# ESP32C6_Xbee.net
KiCad netlist of a schematic drawn in Altium Designer
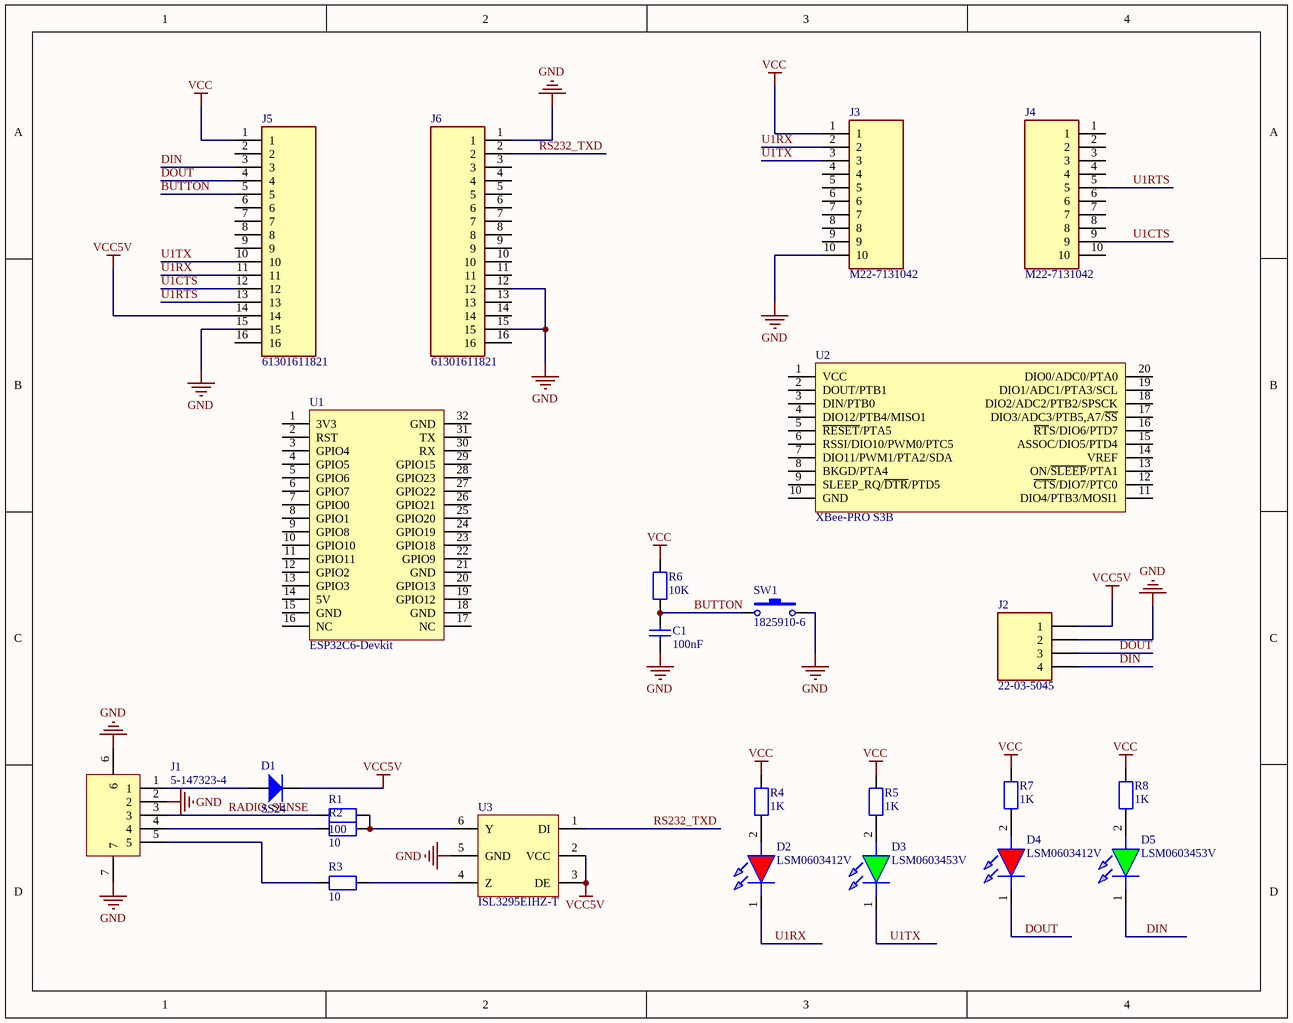
[diagram p0: ESP32C6_Xbee.SchDoc]

(export (version "E")
  (design (tool "Eeschema 10.0.6"))
  (components
    (comp (ref "C1")
      (value "100nF")
      (footprint "C0603")
      (description "0.1 µF ±10% 50V Ceramic Capacitor X7R 0603 (1608 Metric)")
      (fields
        (field (name "MANUFACTURER") "Yageo")
        (field (name "MANUFACTURER PART NUMBER") "CS0603KRX7R9BB104")
      )
      (libsource (lib "ESP32C6-Xbee") (part "100nF ± 10% 50V"))
    )
    (comp (ref "D1")
      (value "SS24")
      (footprint "DO-214AA")
      (description "Schottky Diodes & Rectifiers 2A, 40V, Schottky Rectifier")
      (fields (field (name "MANUFACTURER") "Taiwan Semiconductor"))
      (libsource (lib "ESP32C6-Xbee") (part "SS24"))
    )
    (comp (ref "D2")
      (value "LSM0603412V")
      (footprint "LSM0603412V")
      (description "Red 635nm LED Indication - Discrete 2V 0603 (1608 Metric)")
      (fields (field (name "MANUFACTURER") "Visual Communications Company"))
      (libsource (lib "ESP32C6-Xbee") (part "LSM0603412V"))
    )
    (comp (ref "D3")
      (value "LSM0603453V")
      (footprint "LEDC1608X55N")
      (description "Standard LEDs - SMD SMD 0603 3V 1000mcd GREEN")
      (fields (field (name "MANUFACTURER") "Visual Communications Company"))
      (libsource (lib "ESP32C6-Xbee") (part "LSM0603453V"))
    )
    (comp (ref "D4")
      (value "LSM0603412V")
      (footprint "LSM0603412V")
      (description "Red 635nm LED Indication - Discrete 2V 0603 (1608 Metric)")
      (fields (field (name "MANUFACTURER") "Visual Communications Company"))
      (libsource (lib "ESP32C6-Xbee") (part "LSM0603412V"))
    )
    (comp (ref "D5")
      (value "LSM0603453V")
      (footprint "LEDC1608X55N")
      (description "Standard LEDs - SMD SMD 0603 3V 1000mcd GREEN")
      (fields (field (name "MANUFACTURER") "Visual Communications Company"))
      (libsource (lib "ESP32C6-Xbee") (part "LSM0603453V"))
    )
    (comp (ref "J1")
      (value "5-147323-4")
      (footprint "5-147323-4")
      (description "Connector Header Surface Mount, Right Angle 5 position 0.100\" (2.54mm)")
      (fields (field (name "MANUFACTURER") "TE Connectivity"))
      (libsource (lib "ESP32C6-Xbee") (part "5-147323-4"))
    )
    (comp (ref "J2")
      (value "22-03-5045")
      (footprint "MOLEX_22-03-5045")
      (description "Headers & Wire Housings 2.5 VERT HDR SPOX 4P shrouded")
      (fields (field (name "MANUFACTURER") "Molex"))
      (libsource (lib "ESP32C6-Xbee") (part "22-03-5045"))
    )
    (comp (ref "J3")
      (value "M22-7131042")
      (footprint "M22-7131042")
      (fields (field (name "MANUFACTURER") "Harwin"))
      (libsource (lib "") (part "M22-7131042_1"))
    )
    (comp (ref "J4")
      (value "M22-7131042")
      (footprint "M22-7131042")
      (fields (field (name "MANUFACTURER") "Harwin"))
      (libsource (lib "ESP32C6-Xbee") (part "M22-7131042"))
    )
    (comp (ref "J5")
      (value "61301611821")
      (footprint "61301611821")
      (description "16 Position Header Connector 0.100\" (2.54mm) Through Hole Gold")
      (fields (field (name "MANUFACTURER") "Wurth Elektronik"))
      (libsource (lib "ESP32C6-Xbee") (part "61301611821"))
    )
    (comp (ref "J6")
      (value "61301611821")
      (footprint "61301611821")
      (description "16 Position Header Connector 0.100\" (2.54mm) Through Hole Gold")
      (fields (field (name "MANUFACTURER") "Wurth Elektronik"))
      (libsource (lib "") (part "61301611821_1"))
    )
    (comp (ref "R1")
      (value "100")
      (footprint "R0603")
      (description "100 Ohms ±1% 0.1W, 1/10W Chip Resistor 0603 (1608 Metric) Moisture Resistant Thick Film")
      (fields
        (field (name "MANUFACTURER") "Yageo")
        (field (name "MANUFACTURER PART NUMBER") "RC0603FR-07100RL")
      )
      (libsource (lib "ESP32C6-Xbee") (part "100 Ohms ±1% 0.1W"))
    )
    (comp (ref "R2")
      (value "10")
      (footprint "R0603")
      (description "10 Ohms ±1% 0.1W, 1/10W Chip Resistor 0603 (1608 Metric) Moisture Resistant Thick Film")
      (fields
        (field (name "MANUFACTURER") "Yageo")
        (field (name "MANUFACTURER PART NUMBER") "RC0603FR-0710RL")
      )
      (libsource (lib "ESP32C6-Xbee") (part "10 Ohms ±1% 0.1W"))
    )
    (comp (ref "R3")
      (value "10")
      (footprint "R0603")
      (description "10 Ohms ±1% 0.1W, 1/10W Chip Resistor 0603 (1608 Metric) Moisture Resistant Thick Film")
      (fields
        (field (name "MANUFACTURER") "Yageo")
        (field (name "MANUFACTURER PART NUMBER") "RC0603FR-0710RL")
      )
      (libsource (lib "ESP32C6-Xbee") (part "10 Ohms ±1% 0.1W"))
    )
    (comp (ref "R4")
      (value "1K")
      (footprint "R0603")
      (description "1 kOhms ±1% 0.1W, 1/10W Chip Resistor 0603 (1608 Metric) Moisture Resistant Thick Film")
      (fields
        (field (name "MANUFACTURER") "Yageo")
        (field (name "MANUFACTURER PART NUMBER") "RC0603FR-071KL")
      )
      (libsource (lib "ESP32C6-Xbee") (part "1K Ohms ±1% 0.1W"))
    )
    (comp (ref "R5")
      (value "1K")
      (footprint "R0603")
      (description "1 kOhms ±1% 0.1W, 1/10W Chip Resistor 0603 (1608 Metric) Moisture Resistant Thick Film")
      (fields
        (field (name "MANUFACTURER") "Yageo")
        (field (name "MANUFACTURER PART NUMBER") "RC0603FR-071KL")
      )
      (libsource (lib "ESP32C6-Xbee") (part "1K Ohms ±1% 0.1W"))
    )
    (comp (ref "R6")
      (value "10K")
      (footprint "R0603")
      (description "10 kOhms ±1% 0.1W, 1/10W Chip Resistor 0603 (1608 Metric) Moisture Resistant Thick Film")
      (fields
        (field (name "MANUFACTURER") "Yageo")
        (field (name "MANUFACTURER PART NUMBER") "RC0603FR-0710KL")
      )
      (libsource (lib "ESP32C6-Xbee") (part "10K Ohms ±1% 0.1W"))
    )
    (comp (ref "R7")
      (value "1K")
      (footprint "R0603")
      (description "1 kOhms ±1% 0.1W, 1/10W Chip Resistor 0603 (1608 Metric) Moisture Resistant Thick Film")
      (fields
        (field (name "MANUFACTURER") "Yageo")
        (field (name "MANUFACTURER PART NUMBER") "RC0603FR-071KL")
      )
      (libsource (lib "ESP32C6-Xbee") (part "1K Ohms ±1% 0.1W"))
    )
    (comp (ref "R8")
      (value "1K")
      (footprint "R0603")
      (description "1 kOhms ±1% 0.1W, 1/10W Chip Resistor 0603 (1608 Metric) Moisture Resistant Thick Film")
      (fields
        (field (name "MANUFACTURER") "Yageo")
        (field (name "MANUFACTURER PART NUMBER") "RC0603FR-071KL")
      )
      (libsource (lib "ESP32C6-Xbee") (part "1K Ohms ±1% 0.1W"))
    )
    (comp (ref "SW1")
      (value "1825910-6")
      (footprint "SW_1825910-6-4")
      (description "Tactile Switch SPST-NO Top Actuated Through Hole")
      (fields (field (name "MANUFACTURER") "TE Connectivity"))
      (libsource (lib "ESP32C6-Xbee") (part "1825910-6"))
    )
    (comp (ref "U1")
      (value "ESP32C6-Devkit")
      (footprint "ESP32-C6-Devkit")
      (description "ESP32-C6-MINI-1 Transceiver; Bluetooth® 5 2.4GHz Evaluation Board")
      (fields
        (field (name "MANUFACTURER") "Espressif Systems")
        (field (name "MANUFACTURER PART NUMBER") "ESP32-C6-DevKitM-1-N4")
      )
      (libsource (lib "ESP32C6-Xbee") (part "ESP32C6-Devkit"))
    )
    (comp (ref "U2")
      (value "XBee-PRO S3B")
      (footprint "XBEE(MMS-110-02-L-SV-K-TR)")
      (description "General ISM < 1GHz Transceiver Module 920MHz Antenna Not Included, RP-SMA Through Hole")
      (fields (field (name "MANUFACTURER") "DIGI") (field (name "MANUFACTURER PART NUMBER") "XBP9B-XCST-022"))
      (libsource (lib "ESP32C6-Xbee") (part "XBee-PRO S3B"))
    )
    (comp (ref "U3")
      (value "ISL3295EIHZ-T")
      (footprint "SOT23-6")
      (description "1/0 Driver RS422, RS485 6-SOT")
      (fields (field (name "MANUFACTURER") "Renesas Electronics America Inc"))
      (libsource (lib "ESP32C6-Xbee") (part "ISL3295EIHZ-T"))
    )
  )
  (nets
    (net (code "1") (name "/BUTTON") (class "Default")
      (node (ref "C1") (pin "2") (pinfunction "2_2") (pintype "passive"))
      (node (ref "J5") (pin "5") (pinfunction "5_5") (pintype "passive"))
      (node (ref "R6") (pin "1") (pinfunction "1_1") (pintype "passive"))
      (node (ref "SW1") (pin "1") (pinfunction "1_1") (pintype "passive"))
    )
    (net (code "2") (name "/DIN") (class "Default")
      (node (ref "D5") (pin "1") (pinfunction "K_1") (pintype "passive"))
      (node (ref "J2") (pin "4") (pinfunction "4_4") (pintype "passive"))
      (node (ref "J5") (pin "3") (pinfunction "3_3") (pintype "passive"))
    )
    (net (code "3") (name "/DOUT") (class "Default")
      (node (ref "D4") (pin "1") (pinfunction "K_1") (pintype "passive"))
      (node (ref "J2") (pin "3") (pinfunction "3_3") (pintype "passive"))
      (node (ref "J5") (pin "4") (pinfunction "4_4") (pintype "passive"))
    )
    (net (code "4") (name "/RADIO_SENSE") (class "Default")
      (node (ref "J1") (pin "3") (pinfunction "3_3") (pintype "passive"))
      (node (ref "R1") (pin "1") (pinfunction "1_1") (pintype "passive"))
    )
    (net (code "5") (name "/RS232_TXD") (class "Default")
      (node (ref "J6") (pin "2") (pinfunction "2_2") (pintype "passive"))
      (node (ref "U3") (pin "1") (pinfunction "DI_1") (pintype "passive"))
    )
    (net (code "6") (name "/U1CTS") (class "Default")
      (node (ref "J4") (pin "9") (pinfunction "9_9") (pintype "passive"))
      (node (ref "J5") (pin "12") (pinfunction "12_12") (pintype "passive"))
    )
    (net (code "7") (name "/U1RTS") (class "Default")
      (node (ref "J4") (pin "5") (pinfunction "5_5") (pintype "passive"))
      (node (ref "J5") (pin "13") (pinfunction "13_13") (pintype "passive"))
    )
    (net (code "8") (name "/U1RX") (class "Default")
      (node (ref "D2") (pin "1") (pinfunction "K_1") (pintype "passive"))
      (node (ref "J3") (pin "2") (pinfunction "2_2") (pintype "passive"))
      (node (ref "J5") (pin "11") (pinfunction "11_11") (pintype "passive"))
    )
    (net (code "9") (name "/U1TX") (class "Default")
      (node (ref "D3") (pin "1") (pinfunction "K_1") (pintype "passive"))
      (node (ref "J3") (pin "3") (pinfunction "3_3") (pintype "passive"))
      (node (ref "J5") (pin "10") (pinfunction "10_10") (pintype "passive"))
    )
    (net (code "10") (name "GND") (class "Default")
      (node (ref "C1") (pin "1") (pinfunction "1_1") (pintype "passive"))
      (node (ref "J1") (pin "2") (pinfunction "2_2") (pintype "passive"))
      (node (ref "J1") (pin "6") (pinfunction "6_6") (pintype "passive"))
      (node (ref "J1") (pin "7") (pinfunction "7_7") (pintype "passive"))
      (node (ref "J2") (pin "2") (pinfunction "2_2") (pintype "passive"))
      (node (ref "J3") (pin "10") (pinfunction "10_10") (pintype "passive"))
      (node (ref "J5") (pin "15") (pinfunction "15_15") (pintype "passive"))
      (node (ref "J6") (pin "1") (pinfunction "1_1") (pintype "passive"))
      (node (ref "J6") (pin "12") (pinfunction "12_12") (pintype "passive"))
      (node (ref "J6") (pin "15") (pinfunction "15_15") (pintype "passive"))
      (node (ref "SW1") (pin "2") (pinfunction "2_2") (pintype "passive"))
      (node (ref "U3") (pin "5") (pinfunction "GND_5") (pintype "passive"))
    )
    (net (code "11") (name "Net-(D1-Pad1)") (class "Default")
      (node (ref "D1") (pin "1") (pintype "passive"))
      (node (ref "J1") (pin "1") (pinfunction "1_1") (pintype "passive"))
    )
    (net (code "12") (name "Net-(D2-A)") (class "Default")
      (node (ref "D2") (pin "2") (pinfunction "A_2") (pintype "passive"))
      (node (ref "R4") (pin "1") (pinfunction "1_1") (pintype "passive"))
    )
    (net (code "13") (name "Net-(D3-A)") (class "Default")
      (node (ref "D3") (pin "2") (pinfunction "A_2") (pintype "passive"))
      (node (ref "R5") (pin "1") (pinfunction "1_1") (pintype "passive"))
    )
    (net (code "14") (name "Net-(D4-A)") (class "Default")
      (node (ref "D4") (pin "2") (pinfunction "A_2") (pintype "passive"))
      (node (ref "R7") (pin "1") (pinfunction "1_1") (pintype "passive"))
    )
    (net (code "15") (name "Net-(D5-A)") (class "Default")
      (node (ref "D5") (pin "2") (pinfunction "A_2") (pintype "passive"))
      (node (ref "R8") (pin "1") (pinfunction "1_1") (pintype "passive"))
    )
    (net (code "16") (name "Net-(J1-Pad4)") (class "Default")
      (node (ref "J1") (pin "4") (pinfunction "4_4") (pintype "passive"))
      (node (ref "R2") (pin "1") (pinfunction "1_1") (pintype "passive"))
    )
    (net (code "17") (name "Net-(J1-Pad5)") (class "Default")
      (node (ref "J1") (pin "5") (pinfunction "5_5") (pintype "passive"))
      (node (ref "R3") (pin "1") (pinfunction "1_1") (pintype "passive"))
    )
    (net (code "18") (name "Net-(U3-Y)") (class "Default")
      (node (ref "R1") (pin "2") (pinfunction "2_2") (pintype "passive"))
      (node (ref "R2") (pin "2") (pinfunction "2_2") (pintype "passive"))
      (node (ref "U3") (pin "6") (pinfunction "Y_6") (pintype "passive"))
    )
    (net (code "19") (name "Net-(U3-Z)") (class "Default")
      (node (ref "R3") (pin "2") (pinfunction "2_2") (pintype "passive"))
      (node (ref "U3") (pin "4") (pinfunction "Z_4") (pintype "passive"))
    )
    (net (code "20") (name "VCC") (class "Default")
      (node (ref "J3") (pin "1") (pinfunction "1_1") (pintype "passive"))
      (node (ref "J5") (pin "1") (pinfunction "1_1") (pintype "passive"))
      (node (ref "R4") (pin "2") (pinfunction "2_2") (pintype "passive"))
      (node (ref "R5") (pin "2") (pinfunction "2_2") (pintype "passive"))
      (node (ref "R6") (pin "2") (pinfunction "2_2") (pintype "passive"))
      (node (ref "R7") (pin "2") (pinfunction "2_2") (pintype "passive"))
      (node (ref "R8") (pin "2") (pinfunction "2_2") (pintype "passive"))
    )
    (net (code "21") (name "VCC5V") (class "Default")
      (node (ref "D1") (pin "2") (pintype "passive"))
      (node (ref "J2") (pin "1") (pinfunction "1_1") (pintype "passive"))
      (node (ref "J5") (pin "14") (pinfunction "14_14") (pintype "passive"))
      (node (ref "U3") (pin "2") (pinfunction "VCC_2") (pintype "passive"))
      (node (ref "U3") (pin "3") (pinfunction "DE_3") (pintype "passive"))
    )
    (net (code "22") (name "unconnected-(J3-Pad4)") (class "Default")
      (node (ref "J3") (pin "4") (pinfunction "4_4") (pintype "passive"))
    )
    (net (code "23") (name "unconnected-(J3-Pad5)") (class "Default")
      (node (ref "J3") (pin "5") (pinfunction "5_5") (pintype "passive"))
    )
    (net (code "24") (name "unconnected-(J3-Pad6)") (class "Default")
      (node (ref "J3") (pin "6") (pinfunction "6_6") (pintype "passive"))
    )
    (net (code "25") (name "unconnected-(J3-Pad7)") (class "Default")
      (node (ref "J3") (pin "7") (pinfunction "7_7") (pintype "passive"))
    )
    (net (code "26") (name "unconnected-(J3-Pad8)") (class "Default")
      (node (ref "J3") (pin "8") (pinfunction "8_8") (pintype "passive"))
    )
    (net (code "27") (name "unconnected-(J3-Pad9)") (class "Default")
      (node (ref "J3") (pin "9") (pinfunction "9_9") (pintype "passive"))
    )
    (net (code "28") (name "unconnected-(J4-Pad1)") (class "Default")
      (node (ref "J4") (pin "1") (pinfunction "1_1") (pintype "passive"))
    )
    (net (code "29") (name "unconnected-(J4-Pad2)") (class "Default")
      (node (ref "J4") (pin "2") (pinfunction "2_2") (pintype "passive"))
    )
    (net (code "30") (name "unconnected-(J4-Pad3)") (class "Default")
      (node (ref "J4") (pin "3") (pinfunction "3_3") (pintype "passive"))
    )
    (net (code "31") (name "unconnected-(J4-Pad4)") (class "Default")
      (node (ref "J4") (pin "4") (pinfunction "4_4") (pintype "passive"))
    )
    (net (code "32") (name "unconnected-(J4-Pad6)") (class "Default")
      (node (ref "J4") (pin "6") (pinfunction "6_6") (pintype "passive"))
    )
    (net (code "33") (name "unconnected-(J4-Pad7)") (class "Default")
      (node (ref "J4") (pin "7") (pinfunction "7_7") (pintype "passive"))
    )
    (net (code "34") (name "unconnected-(J4-Pad8)") (class "Default")
      (node (ref "J4") (pin "8") (pinfunction "8_8") (pintype "passive"))
    )
    (net (code "35") (name "unconnected-(J4-Pad10)") (class "Default")
      (node (ref "J4") (pin "10") (pinfunction "10_10") (pintype "passive"))
    )
    (net (code "36") (name "unconnected-(J5-Pad2)") (class "Default")
      (node (ref "J5") (pin "2") (pinfunction "2_2") (pintype "passive"))
    )
    (net (code "37") (name "unconnected-(J5-Pad6)") (class "Default")
      (node (ref "J5") (pin "6") (pinfunction "6_6") (pintype "passive"))
    )
    (net (code "38") (name "unconnected-(J5-Pad7)") (class "Default")
      (node (ref "J5") (pin "7") (pinfunction "7_7") (pintype "passive"))
    )
    (net (code "39") (name "unconnected-(J5-Pad8)") (class "Default")
      (node (ref "J5") (pin "8") (pinfunction "8_8") (pintype "passive"))
    )
    (net (code "40") (name "unconnected-(J5-Pad9)") (class "Default")
      (node (ref "J5") (pin "9") (pinfunction "9_9") (pintype "passive"))
    )
    (net (code "41") (name "unconnected-(J5-Pad16)") (class "Default")
      (node (ref "J5") (pin "16") (pinfunction "16_16") (pintype "passive"))
    )
    (net (code "42") (name "unconnected-(J6-Pad3)") (class "Default")
      (node (ref "J6") (pin "3") (pinfunction "3_3") (pintype "passive"))
    )
    (net (code "43") (name "unconnected-(J6-Pad4)") (class "Default")
      (node (ref "J6") (pin "4") (pinfunction "4_4") (pintype "passive"))
    )
    (net (code "44") (name "unconnected-(J6-Pad5)") (class "Default")
      (node (ref "J6") (pin "5") (pinfunction "5_5") (pintype "passive"))
    )
    (net (code "45") (name "unconnected-(J6-Pad6)") (class "Default")
      (node (ref "J6") (pin "6") (pinfunction "6_6") (pintype "passive"))
    )
    (net (code "46") (name "unconnected-(J6-Pad7)") (class "Default")
      (node (ref "J6") (pin "7") (pinfunction "7_7") (pintype "passive"))
    )
    (net (code "47") (name "unconnected-(J6-Pad8)") (class "Default")
      (node (ref "J6") (pin "8") (pinfunction "8_8") (pintype "passive"))
    )
    (net (code "48") (name "unconnected-(J6-Pad9)") (class "Default")
      (node (ref "J6") (pin "9") (pinfunction "9_9") (pintype "passive"))
    )
    (net (code "49") (name "unconnected-(J6-Pad10)") (class "Default")
      (node (ref "J6") (pin "10") (pinfunction "10_10") (pintype "passive"))
    )
    (net (code "50") (name "unconnected-(J6-Pad11)") (class "Default")
      (node (ref "J6") (pin "11") (pinfunction "11_11") (pintype "passive"))
    )
    (net (code "51") (name "unconnected-(J6-Pad13)") (class "Default")
      (node (ref "J6") (pin "13") (pinfunction "13_13") (pintype "passive"))
    )
    (net (code "52") (name "unconnected-(J6-Pad14)") (class "Default")
      (node (ref "J6") (pin "14") (pinfunction "14_14") (pintype "passive"))
    )
    (net (code "53") (name "unconnected-(J6-Pad16)") (class "Default")
      (node (ref "J6") (pin "16") (pinfunction "16_16") (pintype "passive"))
    )
    (net (code "54") (name "unconnected-(U1-3V3-Pad1)") (class "Default")
      (node (ref "U1") (pin "1") (pinfunction "3V3_1") (pintype "passive"))
    )
    (net (code "55") (name "unconnected-(U1-5V-Pad14)") (class "Default")
      (node (ref "U1") (pin "14") (pinfunction "5V_14") (pintype "passive"))
    )
    (net (code "56") (name "unconnected-(U1-GND-Pad15)") (class "Default")
      (node (ref "U1") (pin "15") (pinfunction "GND_15") (pintype "passive"))
    )
    (net (code "57") (name "unconnected-(U1-GND-Pad18)") (class "Default")
      (node (ref "U1") (pin "18") (pinfunction "GND_18") (pintype "passive"))
    )
    (net (code "58") (name "unconnected-(U1-GND-Pad21)") (class "Default")
      (node (ref "U1") (pin "21") (pinfunction "GND_21") (pintype "passive"))
    )
    (net (code "59") (name "unconnected-(U1-GND-Pad32)") (class "Default")
      (node (ref "U1") (pin "32") (pinfunction "GND_32") (pintype "passive"))
    )
    (net (code "60") (name "unconnected-(U1-GPIO0-Pad7)") (class "Default")
      (node (ref "U1") (pin "7") (pinfunction "GPIO0_7") (pintype "passive"))
    )
    (net (code "61") (name "unconnected-(U1-GPIO1-Pad8)") (class "Default")
      (node (ref "U1") (pin "8") (pinfunction "GPIO1_8") (pintype "passive"))
    )
    (net (code "62") (name "unconnected-(U1-GPIO2-Pad12)") (class "Default")
      (node (ref "U1") (pin "12") (pinfunction "GPIO2_12") (pintype "passive"))
    )
    (net (code "63") (name "unconnected-(U1-GPIO3-Pad13)") (class "Default")
      (node (ref "U1") (pin "13") (pinfunction "GPIO3_13") (pintype "passive"))
    )
    (net (code "64") (name "unconnected-(U1-GPIO4-Pad3)") (class "Default")
      (node (ref "U1") (pin "3") (pinfunction "GPIO4_3") (pintype "passive"))
    )
    (net (code "65") (name "unconnected-(U1-GPIO5-Pad4)") (class "Default")
      (node (ref "U1") (pin "4") (pinfunction "GPIO5_4") (pintype "passive"))
    )
    (net (code "66") (name "unconnected-(U1-GPIO6-Pad5)") (class "Default")
      (node (ref "U1") (pin "5") (pinfunction "GPIO6_5") (pintype "passive"))
    )
    (net (code "67") (name "unconnected-(U1-GPIO7-Pad6)") (class "Default")
      (node (ref "U1") (pin "6") (pinfunction "GPIO7_6") (pintype "passive"))
    )
    (net (code "68") (name "unconnected-(U1-GPIO8-Pad9)") (class "Default")
      (node (ref "U1") (pin "9") (pinfunction "GPIO8_9") (pintype "passive"))
    )
    (net (code "69") (name "unconnected-(U1-GPIO9-Pad22)") (class "Default")
      (node (ref "U1") (pin "22") (pinfunction "GPIO9_22") (pintype "passive"))
    )
    (net (code "70") (name "unconnected-(U1-GPIO10-Pad10)") (class "Default")
      (node (ref "U1") (pin "10") (pinfunction "GPIO10_10") (pintype "passive"))
    )
    (net (code "71") (name "unconnected-(U1-GPIO11-Pad11)") (class "Default")
      (node (ref "U1") (pin "11") (pinfunction "GPIO11_11") (pintype "passive"))
    )
    (net (code "72") (name "unconnected-(U1-GPIO12-Pad19)") (class "Default")
      (node (ref "U1") (pin "19") (pinfunction "GPIO12_19") (pintype "passive"))
    )
    (net (code "73") (name "unconnected-(U1-GPIO13-Pad20)") (class "Default")
      (node (ref "U1") (pin "20") (pinfunction "GPIO13_20") (pintype "passive"))
    )
    (net (code "74") (name "unconnected-(U1-GPIO15-Pad29)") (class "Default")
      (node (ref "U1") (pin "29") (pinfunction "GPIO15_29") (pintype "passive"))
    )
    (net (code "75") (name "unconnected-(U1-GPIO18-Pad23)") (class "Default")
      (node (ref "U1") (pin "23") (pinfunction "GPIO18_23") (pintype "passive"))
    )
    (net (code "76") (name "unconnected-(U1-GPIO19-Pad24)") (class "Default")
      (node (ref "U1") (pin "24") (pinfunction "GPIO19_24") (pintype "passive"))
    )
    (net (code "77") (name "unconnected-(U1-GPIO20-Pad25)") (class "Default")
      (node (ref "U1") (pin "25") (pinfunction "GPIO20_25") (pintype "passive"))
    )
    (net (code "78") (name "unconnected-(U1-GPIO21-Pad26)") (class "Default")
      (node (ref "U1") (pin "26") (pinfunction "GPIO21_26") (pintype "passive"))
    )
    (net (code "79") (name "unconnected-(U1-GPIO22-Pad27)") (class "Default")
      (node (ref "U1") (pin "27") (pinfunction "GPIO22_27") (pintype "passive"))
    )
    (net (code "80") (name "unconnected-(U1-GPIO23-Pad28)") (class "Default")
      (node (ref "U1") (pin "28") (pinfunction "GPIO23_28") (pintype "passive"))
    )
    (net (code "81") (name "unconnected-(U1-NC-Pad16)") (class "Default")
      (node (ref "U1") (pin "16") (pinfunction "NC_16") (pintype "passive"))
    )
    (net (code "82") (name "unconnected-(U1-NC-Pad17)") (class "Default")
      (node (ref "U1") (pin "17") (pinfunction "NC_17") (pintype "passive"))
    )
    (net (code "83") (name "unconnected-(U1-RST-Pad2)") (class "Default")
      (node (ref "U1") (pin "2") (pinfunction "RST_2") (pintype "passive"))
    )
    (net (code "84") (name "unconnected-(U1-RX-Pad30)") (class "Default")
      (node (ref "U1") (pin "30") (pinfunction "RX_30") (pintype "passive"))
    )
    (net (code "85") (name "unconnected-(U1-TX-Pad31)") (class "Default")
      (node (ref "U1") (pin "31") (pinfunction "TX_31") (pintype "passive"))
    )
    (net (code "86") (name "unconnected-(U2-ASSOC{slash}DIO5{slash}PTD4-Pad15)") (class "Default")
      (node (ref "U2") (pin "15") (pinfunction "ASSOC/DIO5/PTD4_15") (pintype "passive"))
    )
    (net (code "87") (name "unconnected-(U2-BKGD{slash}PTA4-Pad8)") (class "Default")
      (node (ref "U2") (pin "8") (pinfunction "BKGD/PTA4_8") (pintype "passive"))
    )
    (net (code "88") (name "unconnected-(U2-DIN{slash}PTB0-Pad3)") (class "Default")
      (node (ref "U2") (pin "3") (pinfunction "DIN/PTB0_3") (pintype "passive"))
    )
    (net (code "89") (name "unconnected-(U2-DIO0{slash}ADC0{slash}PTA0-Pad20)") (class "Default")
      (node (ref "U2") (pin "20") (pinfunction "DIO0/ADC0/PTA0_20") (pintype "passive"))
    )
    (net (code "90") (name "unconnected-(U2-DIO1{slash}ADC1{slash}PTA3{slash}SCL-Pad19)") (class "Default")
      (node (ref "U2") (pin "19") (pinfunction "DIO1/ADC1/PTA3/SCL_19") (pintype "passive"))
    )
    (net (code "91") (name "unconnected-(U2-DIO2{slash}ADC2{slash}PTB2{slash}SPSCK-Pad18)") (class "Default")
      (node (ref "U2") (pin "18") (pinfunction "DIO2/ADC2/PTB2/SPSCK_18") (pintype "passive"))
    )
    (net (code "92") (name "unconnected-(U2-DIO3{slash}ADC3{slash}PTB5,A7{slash}~{SS}-Pad17)") (class "Default")
      (node (ref "U2") (pin "17") (pinfunction "DIO3/ADC3/PTB5,A7/~{SS}_17") (pintype "passive"))
    )
    (net (code "93") (name "unconnected-(U2-DIO4{slash}PTB3{slash}MOSI1-Pad11)") (class "Default")
      (node (ref "U2") (pin "11") (pinfunction "DIO4/PTB3/MOSI1_11") (pintype "passive"))
    )
    (net (code "94") (name "unconnected-(U2-DIO11{slash}PWM1{slash}PTA2{slash}SDA-Pad7)") (class "Default")
      (node (ref "U2") (pin "7") (pinfunction "DIO11/PWM1/PTA2/SDA_7") (pintype "passive"))
    )
    (net (code "95") (name "unconnected-(U2-DIO12{slash}PTB4{slash}MISO1-Pad4)") (class "Default")
      (node (ref "U2") (pin "4") (pinfunction "DIO12/PTB4/MISO1_4") (pintype "passive"))
    )
    (net (code "96") (name "unconnected-(U2-DOUT{slash}PTB1-Pad2)") (class "Default")
      (node (ref "U2") (pin "2") (pinfunction "DOUT/PTB1_2") (pintype "passive"))
    )
    (net (code "97") (name "unconnected-(U2-GND-Pad10)") (class "Default")
      (node (ref "U2") (pin "10") (pinfunction "GND_10") (pintype "passive"))
    )
    (net (code "98") (name "unconnected-(U2-ON{slash}~{SLEEP}{slash}PTA1-Pad13)") (class "Default")
      (node (ref "U2") (pin "13") (pinfunction "ON/~{SLEEP}/PTA1_13") (pintype "passive"))
    )
    (net (code "99") (name "unconnected-(U2-RSSI{slash}DIO10{slash}PWM0{slash}PTC5-Pad6)") (class "Default")
      (node (ref "U2") (pin "6") (pinfunction "RSSI/DIO10/PWM0/PTC5_6") (pintype "passive"))
    )
    (net (code "100") (name "unconnected-(U2-SLEEP_RQ{slash}~{DTR}{slash}PTD5-Pad9)") (class "Default")
      (node (ref "U2") (pin "9") (pinfunction "SLEEP_RQ/~{DTR}/PTD5_9") (pintype "passive"))
    )
    (net (code "101") (name "unconnected-(U2-VCC-Pad1)") (class "Default")
      (node (ref "U2") (pin "1") (pinfunction "VCC_1") (pintype "passive"))
    )
    (net (code "102") (name "unconnected-(U2-VREF-Pad14)") (class "Default")
      (node (ref "U2") (pin "14") (pinfunction "VREF_14") (pintype "passive"))
    )
    (net (code "103") (name "unconnected-(U2-~{CTS}{slash}DIO7{slash}PTC0-Pad12)") (class "Default")
      (node (ref "U2") (pin "12") (pinfunction "~{CTS}/DIO7/PTC0_12") (pintype "passive"))
    )
    (net (code "104") (name "unconnected-(U2-~{RESET}{slash}PTA5-Pad5)") (class "Default")
      (node (ref "U2") (pin "5") (pinfunction "~{RESET}/PTA5_5") (pintype "passive"))
    )
    (net (code "105") (name "unconnected-(U2-~{RT}S{slash}DIO6{slash}PTD7-Pad16)") (class "Default")
      (node (ref "U2") (pin "16") (pinfunction "~{RT}S/DIO6/PTD7_16") (pintype "passive"))
    )
  )
)
